# kam_rx.net
KiCad netlist of a schematic drawn in Altium Designer
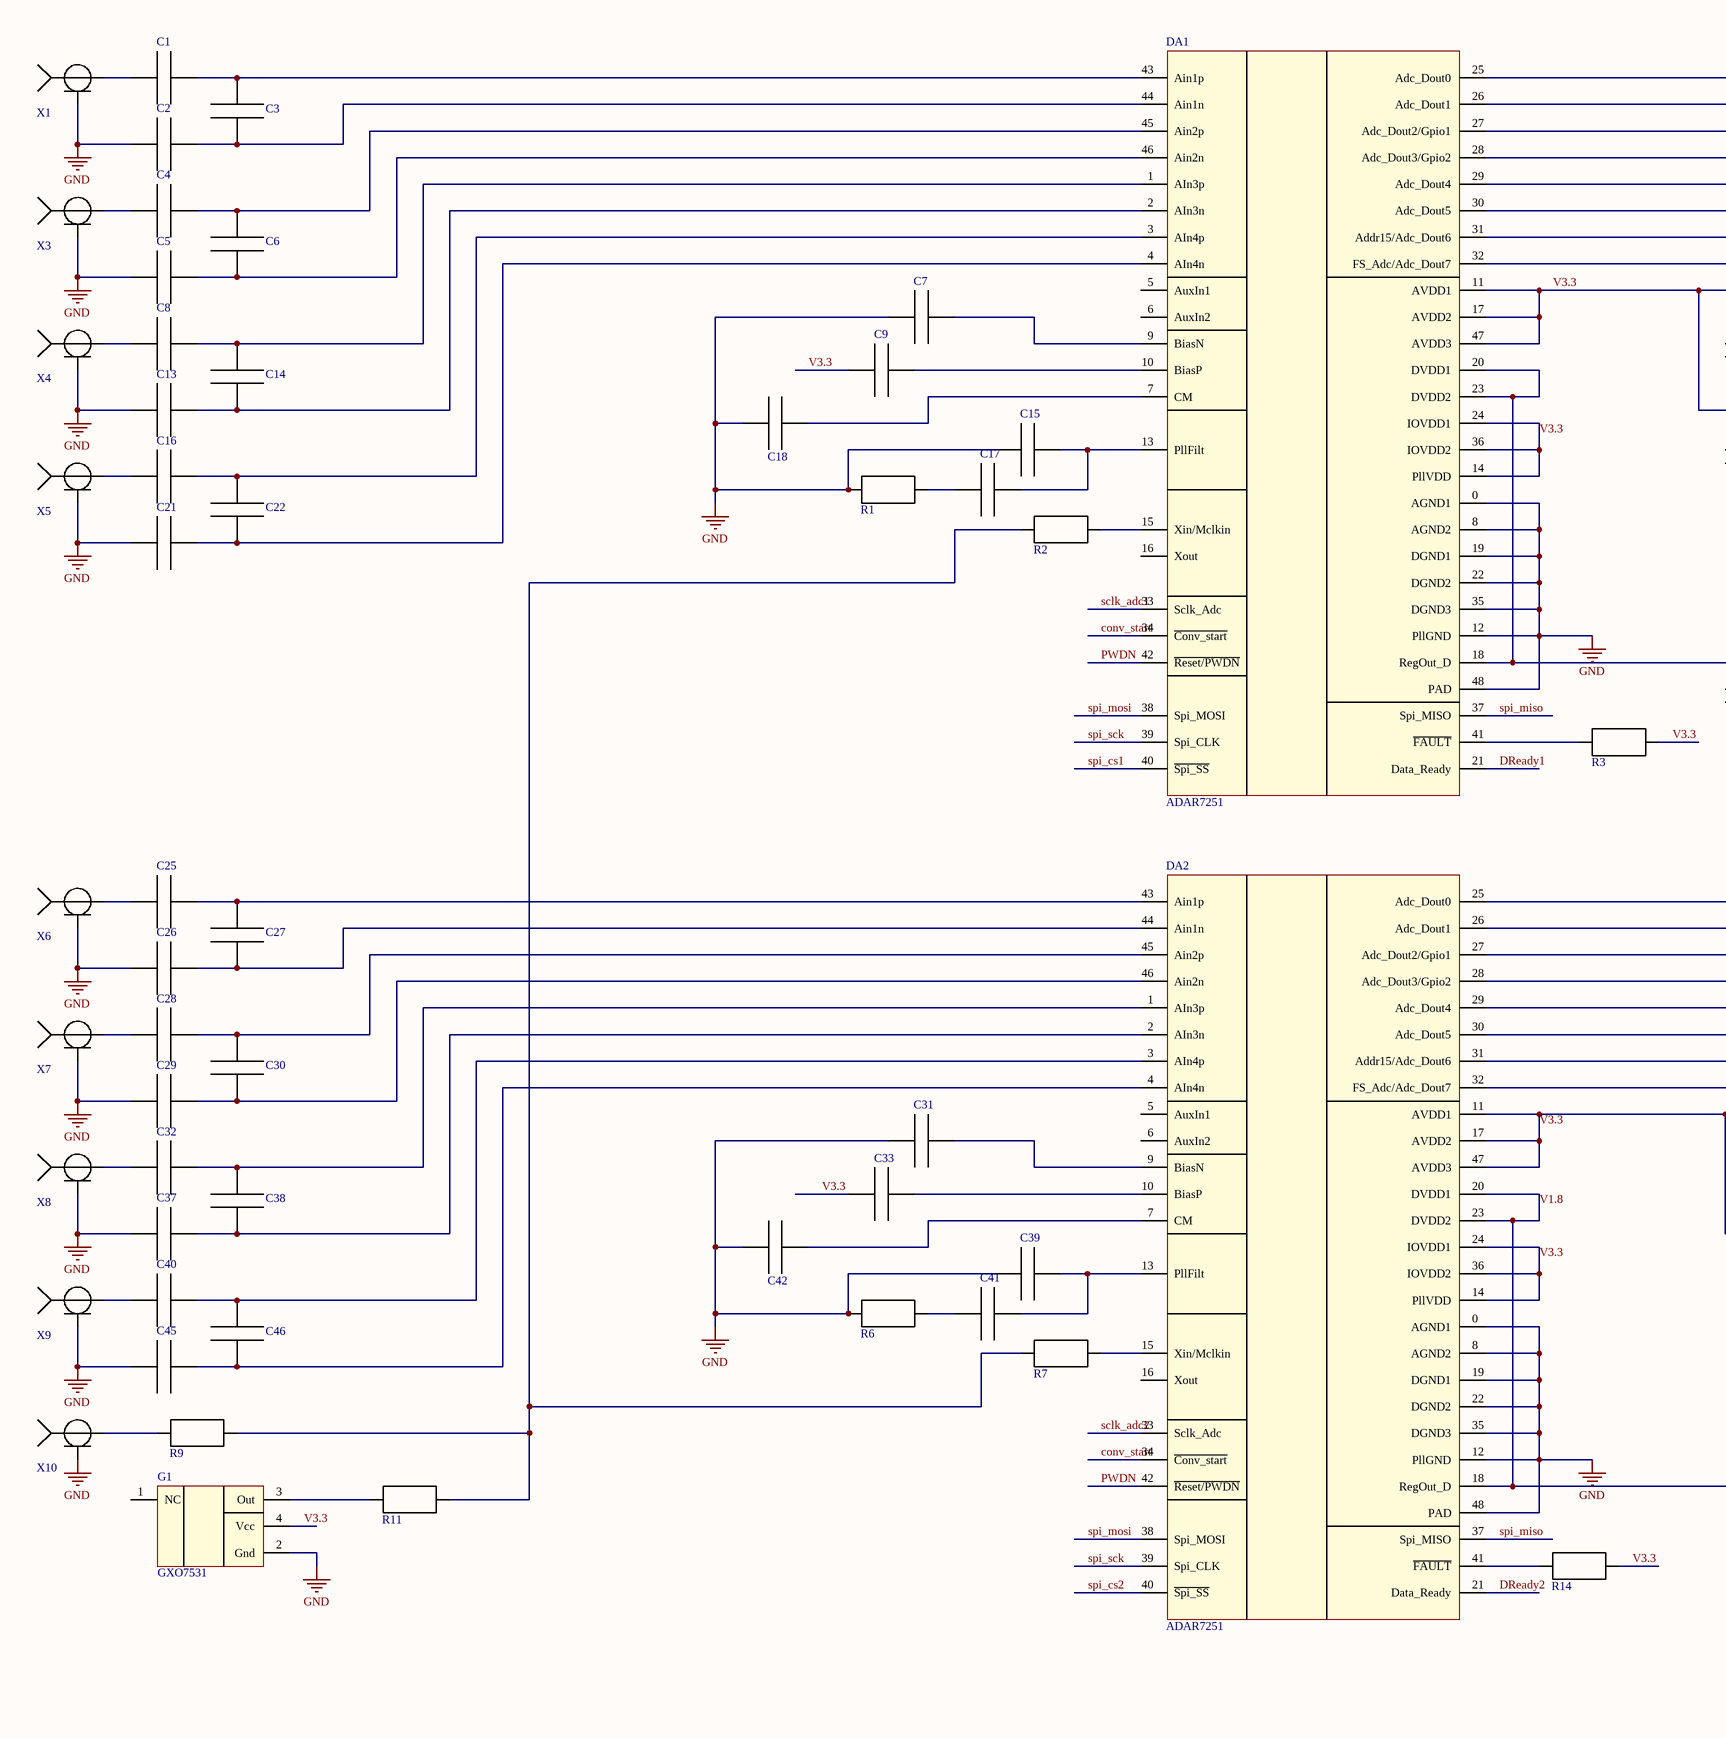
[diagram p0: kam_rx.SchDoc, left]
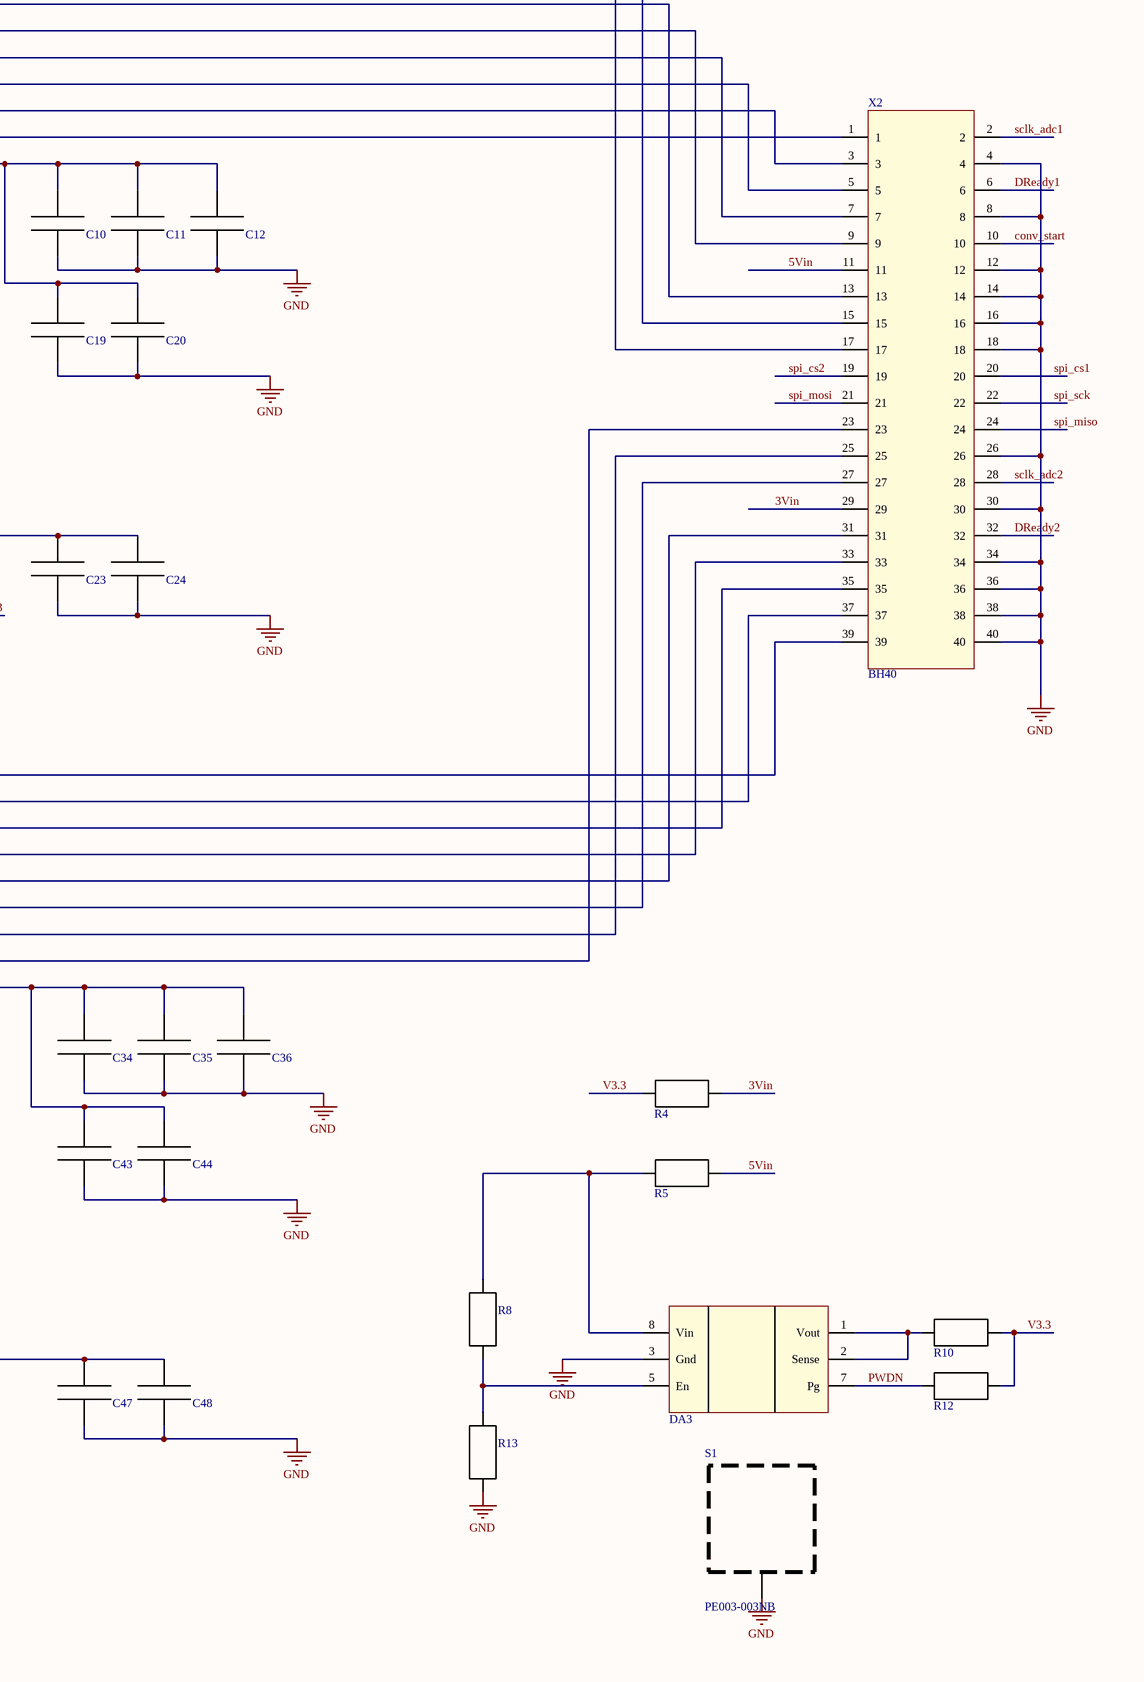
[diagram p1: kam_rx.SchDoc, right]

(export (version "E")
  (design (tool "Eeschema 10.0.6"))
  (components
    (comp (ref "C1")
      (value "C0603")
      (footprint "CAPC1608X06N")
      (libsource (lib "Integrated_Library") (part "C0603"))
    )
    (comp (ref "C2")
      (value "C0603")
      (footprint "CAPC1608X06N")
      (libsource (lib "Integrated_Library") (part "C0603"))
    )
    (comp (ref "C3")
      (value "C0603")
      (footprint "CAPC1608X06N")
      (libsource (lib "Integrated_Library") (part "C0603"))
    )
    (comp (ref "C4")
      (value "C0603")
      (footprint "CAPC1608X06N")
      (libsource (lib "Integrated_Library") (part "C0603"))
    )
    (comp (ref "C5")
      (value "C0603")
      (footprint "CAPC1608X06N")
      (libsource (lib "Integrated_Library") (part "C0603"))
    )
    (comp (ref "C6")
      (value "C0603")
      (footprint "CAPC1608X06N")
      (libsource (lib "Integrated_Library") (part "C0603"))
    )
    (comp (ref "C7")
      (value "C0603")
      (footprint "CAPC1608X06N")
      (libsource (lib "Integrated_Library") (part "C0603"))
    )
    (comp (ref "C8")
      (value "C0603")
      (footprint "CAPC1608X06N")
      (libsource (lib "Integrated_Library") (part "C0603"))
    )
    (comp (ref "C9")
      (value "C0603")
      (footprint "CAPC1608X06N")
      (libsource (lib "Integrated_Library") (part "C0603"))
    )
    (comp (ref "C10")
      (value "C0603")
      (footprint "CAPC1608X06N")
      (libsource (lib "Integrated_Library") (part "C0603"))
    )
    (comp (ref "C11")
      (value "C0603")
      (footprint "CAPC1608X06N")
      (libsource (lib "Integrated_Library") (part "C0603"))
    )
    (comp (ref "C12")
      (value "C0603")
      (footprint "CAPC1608X06N")
      (libsource (lib "Integrated_Library") (part "C0603"))
    )
    (comp (ref "C13")
      (value "C0603")
      (footprint "CAPC1608X06N")
      (libsource (lib "Integrated_Library") (part "C0603"))
    )
    (comp (ref "C14")
      (value "C0603")
      (footprint "CAPC1608X06N")
      (libsource (lib "Integrated_Library") (part "C0603"))
    )
    (comp (ref "C15")
      (value "C0603")
      (footprint "CAPC1608X06N")
      (libsource (lib "Integrated_Library") (part "C0603"))
    )
    (comp (ref "C16")
      (value "C0603")
      (footprint "CAPC1608X06N")
      (libsource (lib "Integrated_Library") (part "C0603"))
    )
    (comp (ref "C17")
      (value "C0603")
      (footprint "CAPC1608X06N")
      (libsource (lib "Integrated_Library") (part "C0603"))
    )
    (comp (ref "C18")
      (value "C0603")
      (footprint "CAPC1608X06N")
      (libsource (lib "Integrated_Library") (part "C0603"))
    )
    (comp (ref "C19")
      (value "C0603")
      (footprint "CAPC1608X06N")
      (libsource (lib "Integrated_Library") (part "C0603"))
    )
    (comp (ref "C20")
      (value "C0603")
      (footprint "CAPC1608X06N")
      (libsource (lib "Integrated_Library") (part "C0603"))
    )
    (comp (ref "C21")
      (value "C0603")
      (footprint "CAPC1608X06N")
      (libsource (lib "Integrated_Library") (part "C0603"))
    )
    (comp (ref "C22")
      (value "C0603")
      (footprint "CAPC1608X06N")
      (libsource (lib "Integrated_Library") (part "C0603"))
    )
    (comp (ref "C23")
      (value "C0603")
      (footprint "CAPC1608X06N")
      (libsource (lib "Integrated_Library") (part "C0603"))
    )
    (comp (ref "C24")
      (value "C0603")
      (footprint "CAPC1608X06N")
      (libsource (lib "Integrated_Library") (part "C0603"))
    )
    (comp (ref "C25")
      (value "C0603")
      (footprint "CAPC1608X06N")
      (libsource (lib "Integrated_Library") (part "C0603"))
    )
    (comp (ref "C26")
      (value "C0603")
      (footprint "CAPC1608X06N")
      (libsource (lib "Integrated_Library") (part "C0603"))
    )
    (comp (ref "C27")
      (value "C0603")
      (footprint "CAPC1608X06N")
      (libsource (lib "Integrated_Library") (part "C0603"))
    )
    (comp (ref "C28")
      (value "C0603")
      (footprint "CAPC1608X06N")
      (libsource (lib "Integrated_Library") (part "C0603"))
    )
    (comp (ref "C29")
      (value "C0603")
      (footprint "CAPC1608X06N")
      (libsource (lib "Integrated_Library") (part "C0603"))
    )
    (comp (ref "C30")
      (value "C0603")
      (footprint "CAPC1608X06N")
      (libsource (lib "Integrated_Library") (part "C0603"))
    )
    (comp (ref "C31")
      (value "C0603")
      (footprint "CAPC1608X06N")
      (libsource (lib "Integrated_Library") (part "C0603"))
    )
    (comp (ref "C32")
      (value "C0603")
      (footprint "CAPC1608X06N")
      (libsource (lib "Integrated_Library") (part "C0603"))
    )
    (comp (ref "C33")
      (value "C0603")
      (footprint "CAPC1608X06N")
      (libsource (lib "Integrated_Library") (part "C0603"))
    )
    (comp (ref "C34")
      (value "C0603")
      (footprint "CAPC1608X06N")
      (libsource (lib "Integrated_Library") (part "C0603"))
    )
    (comp (ref "C35")
      (value "C0603")
      (footprint "CAPC1608X06N")
      (libsource (lib "Integrated_Library") (part "C0603"))
    )
    (comp (ref "C36")
      (value "C0603")
      (footprint "CAPC1608X06N")
      (libsource (lib "Integrated_Library") (part "C0603"))
    )
    (comp (ref "C37")
      (value "C0603")
      (footprint "CAPC1608X06N")
      (libsource (lib "Integrated_Library") (part "C0603"))
    )
    (comp (ref "C38")
      (value "C0603")
      (footprint "CAPC1608X06N")
      (libsource (lib "Integrated_Library") (part "C0603"))
    )
    (comp (ref "C39")
      (value "C0603")
      (footprint "CAPC1608X06N")
      (libsource (lib "Integrated_Library") (part "C0603"))
    )
    (comp (ref "C40")
      (value "C0603")
      (footprint "CAPC1608X06N")
      (libsource (lib "Integrated_Library") (part "C0603"))
    )
    (comp (ref "C41")
      (value "C0603")
      (footprint "CAPC1608X06N")
      (libsource (lib "Integrated_Library") (part "C0603"))
    )
    (comp (ref "C42")
      (value "C0603")
      (footprint "CAPC1608X06N")
      (libsource (lib "Integrated_Library") (part "C0603"))
    )
    (comp (ref "C43")
      (value "C0603")
      (footprint "CAPC1608X06N")
      (libsource (lib "Integrated_Library") (part "C0603"))
    )
    (comp (ref "C44")
      (value "C0603")
      (footprint "CAPC1608X06N")
      (libsource (lib "Integrated_Library") (part "C0603"))
    )
    (comp (ref "C45")
      (value "C0603")
      (footprint "CAPC1608X06N")
      (libsource (lib "Integrated_Library") (part "C0603"))
    )
    (comp (ref "C46")
      (value "C0603")
      (footprint "CAPC1608X06N")
      (libsource (lib "Integrated_Library") (part "C0603"))
    )
    (comp (ref "C47")
      (value "C0603")
      (footprint "CAPC1608X06N")
      (libsource (lib "Integrated_Library") (part "C0603"))
    )
    (comp (ref "C48")
      (value "C0603")
      (footprint "CAPC1608X06N")
      (libsource (lib "Integrated_Library") (part "C0603"))
    )
    (comp (ref "DA1")
      (value "ADAR7251")
      (footprint "PQFN50P700X700X100_HS-49N")
      (libsource (lib "Integrated_Library") (part "ADAR7251"))
    )
    (comp (ref "DA2")
      (value "ADAR7251")
      (footprint "PQFN50P700X700X100_HS-49N")
      (libsource (lib "Integrated_Library") (part "ADAR7251"))
    )
    (comp (ref "DA3")
      (value "ADP7104")
      (footprint "SOIC127P600X165_HS-9N")
      (libsource (lib "Integrated_Library") (part "ADP7104"))
    )
    (comp (ref "G1")
      (value "GXO7531")
      (footprint "DFN400P700X145-4N")
      (libsource (lib "Integrated_Library") (part "GXO7531"))
    )
    (comp (ref "R1")
      (value "R0603")
      (footprint "RESC1608X06N")
      (libsource (lib "Integrated_Library") (part "R0603"))
    )
    (comp (ref "R2")
      (value "R0603")
      (footprint "RESC1608X06N")
      (libsource (lib "Integrated_Library") (part "R0603"))
    )
    (comp (ref "R3")
      (value "R0603")
      (footprint "RESC1608X06N")
      (libsource (lib "Integrated_Library") (part "R0603"))
    )
    (comp (ref "R4")
      (value "R0603")
      (footprint "RESC1608X06N")
      (libsource (lib "Integrated_Library") (part "R0603"))
    )
    (comp (ref "R5")
      (value "R0603")
      (footprint "RESC1608X06N")
      (libsource (lib "Integrated_Library") (part "R0603"))
    )
    (comp (ref "R6")
      (value "R0603")
      (footprint "RESC1608X06N")
      (libsource (lib "Integrated_Library") (part "R0603"))
    )
    (comp (ref "R7")
      (value "R0603")
      (footprint "RESC1608X06N")
      (libsource (lib "Integrated_Library") (part "R0603"))
    )
    (comp (ref "R8")
      (value "R0603")
      (footprint "RESC1608X06N")
      (libsource (lib "Integrated_Library") (part "R0603"))
    )
    (comp (ref "R9")
      (value "R0603")
      (footprint "RESC1608X06N")
      (libsource (lib "Integrated_Library") (part "R0603"))
    )
    (comp (ref "R10")
      (value "R0603")
      (footprint "RESC1608X06N")
      (libsource (lib "Integrated_Library") (part "R0603"))
    )
    (comp (ref "R11")
      (value "R0603")
      (footprint "RESC1608X06N")
      (libsource (lib "Integrated_Library") (part "R0603"))
    )
    (comp (ref "R12")
      (value "R0603")
      (footprint "RESC1608X06N")
      (libsource (lib "Integrated_Library") (part "R0603"))
    )
    (comp (ref "R13")
      (value "R0603")
      (footprint "RESC1608X06N")
      (libsource (lib "Integrated_Library") (part "R0603"))
    )
    (comp (ref "R14")
      (value "R0603")
      (footprint "RESC1608X06N")
      (libsource (lib "Integrated_Library") (part "R0603"))
    )
    (comp (ref "S1")
      (value "PE003-003NB")
      (footprint "PE003-003NB")
      (libsource (lib "Integrated_Library") (part "PE003-003NB"))
    )
    (comp (ref "X1")
      (value "MCX 1085221-1")
      (footprint "MCX")
      (libsource (lib "Integrated_Library") (part "MCX 1085221-1"))
    )
    (comp (ref "X2") (value "BH40") (footprint "BH40") (libsource (lib "Integrated_Library") (part "BH40")))
    (comp (ref "X3")
      (value "MCX 1085221-1")
      (footprint "MCX")
      (libsource (lib "Integrated_Library") (part "MCX 1085221-1"))
    )
    (comp (ref "X4")
      (value "MCX 1085221-1")
      (footprint "MCX")
      (libsource (lib "Integrated_Library") (part "MCX 1085221-1"))
    )
    (comp (ref "X5")
      (value "MCX 1085221-1")
      (footprint "MCX")
      (libsource (lib "Integrated_Library") (part "MCX 1085221-1"))
    )
    (comp (ref "X6")
      (value "MCX 1085221-1")
      (footprint "MCX")
      (libsource (lib "Integrated_Library") (part "MCX 1085221-1"))
    )
    (comp (ref "X7")
      (value "MCX 1085221-1")
      (footprint "MCX")
      (libsource (lib "Integrated_Library") (part "MCX 1085221-1"))
    )
    (comp (ref "X8")
      (value "MCX 1085221-1")
      (footprint "MCX")
      (libsource (lib "Integrated_Library") (part "MCX 1085221-1"))
    )
    (comp (ref "X9")
      (value "MCX 1085221-1")
      (footprint "MCX")
      (libsource (lib "Integrated_Library") (part "MCX 1085221-1"))
    )
    (comp (ref "X10")
      (value "MCX 1085221-1")
      (footprint "MCX")
      (libsource (lib "Integrated_Library") (part "MCX 1085221-1"))
    )
  )
  (nets
    (net (code "1") (name "/3Vin") (class "Default")
      (node (ref "R4") (pin "1") (pinfunction "1_1") (pintype "passive"))
      (node (ref "X2") (pin "29") (pinfunction "29_29") (pintype "passive"))
    )
    (net (code "2") (name "/5Vin") (class "Default")
      (node (ref "R5") (pin "1") (pinfunction "1_1") (pintype "passive"))
      (node (ref "X2") (pin "11") (pinfunction "11_11") (pintype "passive"))
    )
    (net (code "3") (name "/DReady1") (class "Default")
      (node (ref "DA1") (pin "21") (pinfunction "Data_Ready_21") (pintype "passive"))
      (node (ref "X2") (pin "6") (pinfunction "6_6") (pintype "passive"))
    )
    (net (code "4") (name "/DReady2") (class "Default")
      (node (ref "DA2") (pin "21") (pinfunction "Data_Ready_21") (pintype "passive"))
      (node (ref "X2") (pin "32") (pinfunction "32_32") (pintype "passive"))
    )
    (net (code "5") (name "/PWDN") (class "Default")
      (node (ref "DA1") (pin "42") (pinfunction "~{Reset/PWDN}_42") (pintype "passive"))
      (node (ref "DA2") (pin "42") (pinfunction "~{Reset/PWDN}_42") (pintype "passive"))
      (node (ref "DA3") (pin "7") (pinfunction "Pg_7") (pintype "passive"))
      (node (ref "R12") (pin "2") (pinfunction "2_2") (pintype "passive"))
    )
    (net (code "6") (name "/V1.8") (class "Default")
      (node (ref "C47") (pin "1") (pinfunction "1_1") (pintype "passive"))
      (node (ref "C48") (pin "1") (pinfunction "1_1") (pintype "passive"))
      (node (ref "DA2") (pin "18") (pinfunction "RegOut_D_18") (pintype "passive"))
      (node (ref "DA2") (pin "20") (pinfunction "DVDD1_20") (pintype "passive"))
      (node (ref "DA2") (pin "23") (pinfunction "DVDD2_23") (pintype "passive"))
    )
    (net (code "7") (name "/V3.3") (class "Default")
      (node (ref "C10") (pin "1") (pinfunction "1_1") (pintype "passive"))
      (node (ref "C11") (pin "1") (pinfunction "1_1") (pintype "passive"))
      (node (ref "C12") (pin "1") (pinfunction "1_1") (pintype "passive"))
      (node (ref "C19") (pin "1") (pinfunction "1_1") (pintype "passive"))
      (node (ref "C20") (pin "1") (pinfunction "1_1") (pintype "passive"))
      (node (ref "C33") (pin "1") (pinfunction "1_1") (pintype "passive"))
      (node (ref "C34") (pin "1") (pinfunction "1_1") (pintype "passive"))
      (node (ref "C35") (pin "1") (pinfunction "1_1") (pintype "passive"))
      (node (ref "C36") (pin "1") (pinfunction "1_1") (pintype "passive"))
      (node (ref "C43") (pin "1") (pinfunction "1_1") (pintype "passive"))
      (node (ref "C44") (pin "1") (pinfunction "1_1") (pintype "passive"))
      (node (ref "C9") (pin "1") (pinfunction "1_1") (pintype "passive"))
      (node (ref "DA1") (pin "11") (pinfunction "AVDD1_11") (pintype "passive"))
      (node (ref "DA1") (pin "14") (pinfunction "PllVDD_14") (pintype "passive"))
      (node (ref "DA1") (pin "17") (pinfunction "AVDD2_17") (pintype "passive"))
      (node (ref "DA1") (pin "24") (pinfunction "IOVDD1_24") (pintype "passive"))
      (node (ref "DA1") (pin "36") (pinfunction "IOVDD2_36") (pintype "passive"))
      (node (ref "DA1") (pin "47") (pinfunction "AVDD3_47") (pintype "passive"))
      (node (ref "DA2") (pin "11") (pinfunction "AVDD1_11") (pintype "passive"))
      (node (ref "DA2") (pin "14") (pinfunction "PllVDD_14") (pintype "passive"))
      (node (ref "DA2") (pin "17") (pinfunction "AVDD2_17") (pintype "passive"))
      (node (ref "DA2") (pin "24") (pinfunction "IOVDD1_24") (pintype "passive"))
      (node (ref "DA2") (pin "36") (pinfunction "IOVDD2_36") (pintype "passive"))
      (node (ref "DA2") (pin "47") (pinfunction "AVDD3_47") (pintype "passive"))
      (node (ref "G1") (pin "4") (pinfunction "Vcc_4") (pintype "passive"))
      (node (ref "R10") (pin "1") (pinfunction "1_1") (pintype "passive"))
      (node (ref "R12") (pin "1") (pinfunction "1_1") (pintype "passive"))
      (node (ref "R14") (pin "1") (pinfunction "1_1") (pintype "passive"))
      (node (ref "R3") (pin "1") (pinfunction "1_1") (pintype "passive"))
      (node (ref "R4") (pin "2") (pinfunction "2_2") (pintype "passive"))
    )
    (net (code "8") (name "/conv_start") (class "Default")
      (node (ref "DA1") (pin "34") (pinfunction "~{Conv_start}_34") (pintype "passive"))
      (node (ref "DA2") (pin "34") (pinfunction "~{Conv_start}_34") (pintype "passive"))
      (node (ref "X2") (pin "10") (pinfunction "10_10") (pintype "passive"))
    )
    (net (code "9") (name "/sclk_adc1") (class "Default")
      (node (ref "DA1") (pin "33") (pinfunction "Sclk_Adc_33") (pintype "passive"))
      (node (ref "X2") (pin "2") (pinfunction "2_2") (pintype "passive"))
    )
    (net (code "10") (name "/sclk_adc2") (class "Default")
      (node (ref "DA2") (pin "33") (pinfunction "Sclk_Adc_33") (pintype "passive"))
      (node (ref "X2") (pin "28") (pinfunction "28_28") (pintype "passive"))
    )
    (net (code "11") (name "/spi_cs1") (class "Default")
      (node (ref "DA1") (pin "40") (pinfunction "~{Spi_SS}_40") (pintype "passive"))
      (node (ref "X2") (pin "20") (pinfunction "20_20") (pintype "passive"))
    )
    (net (code "12") (name "/spi_cs2") (class "Default")
      (node (ref "DA2") (pin "40") (pinfunction "~{Spi_SS}_40") (pintype "passive"))
      (node (ref "X2") (pin "19") (pinfunction "19_19") (pintype "passive"))
    )
    (net (code "13") (name "/spi_miso") (class "Default")
      (node (ref "DA1") (pin "37") (pinfunction "Spi_MISO_37") (pintype "passive"))
      (node (ref "DA2") (pin "37") (pinfunction "Spi_MISO_37") (pintype "passive"))
      (node (ref "X2") (pin "24") (pinfunction "24_24") (pintype "passive"))
    )
    (net (code "14") (name "/spi_mosi") (class "Default")
      (node (ref "DA1") (pin "38") (pinfunction "Spi_MOSI_38") (pintype "passive"))
      (node (ref "DA2") (pin "38") (pinfunction "Spi_MOSI_38") (pintype "passive"))
      (node (ref "X2") (pin "21") (pinfunction "21_21") (pintype "passive"))
    )
    (net (code "15") (name "/spi_sck") (class "Default")
      (node (ref "DA1") (pin "39") (pinfunction "Spi_CLK_39") (pintype "passive"))
      (node (ref "DA2") (pin "39") (pinfunction "Spi_CLK_39") (pintype "passive"))
      (node (ref "X2") (pin "22") (pinfunction "22_22") (pintype "passive"))
    )
    (net (code "16") (name "GND") (class "Default")
      (node (ref "C10") (pin "2") (pinfunction "2_2") (pintype "passive"))
      (node (ref "C11") (pin "2") (pinfunction "2_2") (pintype "passive"))
      (node (ref "C12") (pin "2") (pinfunction "2_2") (pintype "passive"))
      (node (ref "C13") (pin "1") (pinfunction "1_1") (pintype "passive"))
      (node (ref "C15") (pin "1") (pinfunction "1_1") (pintype "passive"))
      (node (ref "C18") (pin "2") (pinfunction "2_2") (pintype "passive"))
      (node (ref "C19") (pin "2") (pinfunction "2_2") (pintype "passive"))
      (node (ref "C2") (pin "1") (pinfunction "1_1") (pintype "passive"))
      (node (ref "C20") (pin "2") (pinfunction "2_2") (pintype "passive"))
      (node (ref "C21") (pin "1") (pinfunction "1_1") (pintype "passive"))
      (node (ref "C23") (pin "2") (pinfunction "2_2") (pintype "passive"))
      (node (ref "C24") (pin "2") (pinfunction "2_2") (pintype "passive"))
      (node (ref "C26") (pin "1") (pinfunction "1_1") (pintype "passive"))
      (node (ref "C29") (pin "1") (pinfunction "1_1") (pintype "passive"))
      (node (ref "C31") (pin "1") (pinfunction "1_1") (pintype "passive"))
      (node (ref "C34") (pin "2") (pinfunction "2_2") (pintype "passive"))
      (node (ref "C35") (pin "2") (pinfunction "2_2") (pintype "passive"))
      (node (ref "C36") (pin "2") (pinfunction "2_2") (pintype "passive"))
      (node (ref "C37") (pin "1") (pinfunction "1_1") (pintype "passive"))
      (node (ref "C39") (pin "1") (pinfunction "1_1") (pintype "passive"))
      (node (ref "C42") (pin "2") (pinfunction "2_2") (pintype "passive"))
      (node (ref "C43") (pin "2") (pinfunction "2_2") (pintype "passive"))
      (node (ref "C44") (pin "2") (pinfunction "2_2") (pintype "passive"))
      (node (ref "C45") (pin "1") (pinfunction "1_1") (pintype "passive"))
      (node (ref "C47") (pin "2") (pinfunction "2_2") (pintype "passive"))
      (node (ref "C48") (pin "2") (pinfunction "2_2") (pintype "passive"))
      (node (ref "C5") (pin "1") (pinfunction "1_1") (pintype "passive"))
      (node (ref "C7") (pin "1") (pinfunction "1_1") (pintype "passive"))
      (node (ref "DA1") (pin "0") (pinfunction "AGND1_0") (pintype "passive"))
      (node (ref "DA1") (pin "12") (pinfunction "PllGND_12") (pintype "passive"))
      (node (ref "DA1") (pin "19") (pinfunction "DGND1_19") (pintype "passive"))
      (node (ref "DA1") (pin "22") (pinfunction "DGND2_22") (pintype "passive"))
      (node (ref "DA1") (pin "35") (pinfunction "DGND3_35") (pintype "passive"))
      (node (ref "DA1") (pin "48") (pinfunction "PAD_48") (pintype "passive"))
      (node (ref "DA1") (pin "8") (pinfunction "AGND2_8") (pintype "passive"))
      (node (ref "DA2") (pin "0") (pinfunction "AGND1_0") (pintype "passive"))
      (node (ref "DA2") (pin "12") (pinfunction "PllGND_12") (pintype "passive"))
      (node (ref "DA2") (pin "19") (pinfunction "DGND1_19") (pintype "passive"))
      (node (ref "DA2") (pin "22") (pinfunction "DGND2_22") (pintype "passive"))
      (node (ref "DA2") (pin "35") (pinfunction "DGND3_35") (pintype "passive"))
      (node (ref "DA2") (pin "48") (pinfunction "PAD_48") (pintype "passive"))
      (node (ref "DA2") (pin "8") (pinfunction "AGND2_8") (pintype "passive"))
      (node (ref "DA3") (pin "3") (pinfunction "Gnd_3") (pintype "passive"))
      (node (ref "G1") (pin "2") (pinfunction "Gnd_2") (pintype "passive"))
      (node (ref "R1") (pin "2") (pinfunction "2_2") (pintype "passive"))
      (node (ref "R13") (pin "2") (pinfunction "2_2") (pintype "passive"))
      (node (ref "R6") (pin "2") (pinfunction "2_2") (pintype "passive"))
      (node (ref "S1") (pin "0") (pinfunction "0_0") (pintype "passive"))
      (node (ref "X1") (pin "2") (pinfunction "2_2") (pintype "passive"))
      (node (ref "X10") (pin "2") (pinfunction "2_2") (pintype "passive"))
      (node (ref "X2") (pin "12") (pinfunction "12_12") (pintype "passive"))
      (node (ref "X2") (pin "14") (pinfunction "14_14") (pintype "passive"))
      (node (ref "X2") (pin "16") (pinfunction "16_16") (pintype "passive"))
      (node (ref "X2") (pin "18") (pinfunction "18_18") (pintype "passive"))
      (node (ref "X2") (pin "26") (pinfunction "26_26") (pintype "passive"))
      (node (ref "X2") (pin "30") (pinfunction "30_30") (pintype "passive"))
      (node (ref "X2") (pin "34") (pinfunction "34_34") (pintype "passive"))
      (node (ref "X2") (pin "36") (pinfunction "36_36") (pintype "passive"))
      (node (ref "X2") (pin "38") (pinfunction "38_38") (pintype "passive"))
      (node (ref "X2") (pin "4") (pinfunction "4_4") (pintype "passive"))
      (node (ref "X2") (pin "40") (pinfunction "40_40") (pintype "passive"))
      (node (ref "X2") (pin "8") (pinfunction "8_8") (pintype "passive"))
      (node (ref "X3") (pin "2") (pinfunction "2_2") (pintype "passive"))
      (node (ref "X4") (pin "2") (pinfunction "2_2") (pintype "passive"))
      (node (ref "X5") (pin "2") (pinfunction "2_2") (pintype "passive"))
      (node (ref "X6") (pin "2") (pinfunction "2_2") (pintype "passive"))
      (node (ref "X7") (pin "2") (pinfunction "2_2") (pintype "passive"))
      (node (ref "X8") (pin "2") (pinfunction "2_2") (pintype "passive"))
      (node (ref "X9") (pin "2") (pinfunction "2_2") (pintype "passive"))
    )
    (net (code "17") (name "Net-(C1-Pad1)") (class "Default")
      (node (ref "C1") (pin "1") (pinfunction "1_1") (pintype "passive"))
      (node (ref "X1") (pin "1") (pinfunction "1_1") (pintype "passive"))
    )
    (net (code "18") (name "Net-(C4-Pad1)") (class "Default")
      (node (ref "C4") (pin "1") (pinfunction "1_1") (pintype "passive"))
      (node (ref "X3") (pin "1") (pinfunction "1_1") (pintype "passive"))
    )
    (net (code "19") (name "Net-(C8-Pad1)") (class "Default")
      (node (ref "C8") (pin "1") (pinfunction "1_1") (pintype "passive"))
      (node (ref "X4") (pin "1") (pinfunction "1_1") (pintype "passive"))
    )
    (net (code "20") (name "Net-(C16-Pad1)") (class "Default")
      (node (ref "C16") (pin "1") (pinfunction "1_1") (pintype "passive"))
      (node (ref "X5") (pin "1") (pinfunction "1_1") (pintype "passive"))
    )
    (net (code "21") (name "Net-(C17-Pad1)") (class "Default")
      (node (ref "C17") (pin "1") (pinfunction "1_1") (pintype "passive"))
      (node (ref "R1") (pin "1") (pinfunction "1_1") (pintype "passive"))
    )
    (net (code "22") (name "Net-(C25-Pad1)") (class "Default")
      (node (ref "C25") (pin "1") (pinfunction "1_1") (pintype "passive"))
      (node (ref "X6") (pin "1") (pinfunction "1_1") (pintype "passive"))
    )
    (net (code "23") (name "Net-(C28-Pad1)") (class "Default")
      (node (ref "C28") (pin "1") (pinfunction "1_1") (pintype "passive"))
      (node (ref "X7") (pin "1") (pinfunction "1_1") (pintype "passive"))
    )
    (net (code "24") (name "Net-(C32-Pad1)") (class "Default")
      (node (ref "C32") (pin "1") (pinfunction "1_1") (pintype "passive"))
      (node (ref "X8") (pin "1") (pinfunction "1_1") (pintype "passive"))
    )
    (net (code "25") (name "Net-(C40-Pad1)") (class "Default")
      (node (ref "C40") (pin "1") (pinfunction "1_1") (pintype "passive"))
      (node (ref "X9") (pin "1") (pinfunction "1_1") (pintype "passive"))
    )
    (net (code "26") (name "Net-(C41-Pad1)") (class "Default")
      (node (ref "C41") (pin "1") (pinfunction "1_1") (pintype "passive"))
      (node (ref "R6") (pin "1") (pinfunction "1_1") (pintype "passive"))
    )
    (net (code "27") (name "Net-(DA1-AIn3n)") (class "Default")
      (node (ref "C13") (pin "2") (pinfunction "2_2") (pintype "passive"))
      (node (ref "C14") (pin "1") (pinfunction "1_1") (pintype "passive"))
      (node (ref "DA1") (pin "2") (pinfunction "AIn3n_2") (pintype "passive"))
    )
    (net (code "28") (name "Net-(DA1-AIn3p)") (class "Default")
      (node (ref "C14") (pin "2") (pinfunction "2_2") (pintype "passive"))
      (node (ref "C8") (pin "2") (pinfunction "2_2") (pintype "passive"))
      (node (ref "DA1") (pin "1") (pinfunction "AIn3p_1") (pintype "passive"))
    )
    (net (code "29") (name "Net-(DA1-AIn4n)") (class "Default")
      (node (ref "C21") (pin "2") (pinfunction "2_2") (pintype "passive"))
      (node (ref "C22") (pin "1") (pinfunction "1_1") (pintype "passive"))
      (node (ref "DA1") (pin "4") (pinfunction "AIn4n_4") (pintype "passive"))
    )
    (net (code "30") (name "Net-(DA1-AIn4p)") (class "Default")
      (node (ref "C16") (pin "2") (pinfunction "2_2") (pintype "passive"))
      (node (ref "C22") (pin "2") (pinfunction "2_2") (pintype "passive"))
      (node (ref "DA1") (pin "3") (pinfunction "AIn4p_3") (pintype "passive"))
    )
    (net (code "31") (name "Net-(DA1-Adc_Dout0)") (class "Default")
      (node (ref "DA1") (pin "25") (pinfunction "Adc_Dout0_25") (pintype "passive"))
      (node (ref "X2") (pin "17") (pinfunction "17_17") (pintype "passive"))
    )
    (net (code "32") (name "Net-(DA1-Adc_Dout1)") (class "Default")
      (node (ref "DA1") (pin "26") (pinfunction "Adc_Dout1_26") (pintype "passive"))
      (node (ref "X2") (pin "15") (pinfunction "15_15") (pintype "passive"))
    )
    (net (code "33") (name "Net-(DA1-Adc_Dout2{slash}Gpio1)") (class "Default")
      (node (ref "DA1") (pin "27") (pinfunction "Adc_Dout2/Gpio1_27") (pintype "passive"))
      (node (ref "X2") (pin "13") (pinfunction "13_13") (pintype "passive"))
    )
    (net (code "34") (name "Net-(DA1-Adc_Dout3{slash}Gpio2)") (class "Default")
      (node (ref "DA1") (pin "28") (pinfunction "Adc_Dout3/Gpio2_28") (pintype "passive"))
      (node (ref "X2") (pin "9") (pinfunction "9_9") (pintype "passive"))
    )
    (net (code "35") (name "Net-(DA1-Adc_Dout4)") (class "Default")
      (node (ref "DA1") (pin "29") (pinfunction "Adc_Dout4_29") (pintype "passive"))
      (node (ref "X2") (pin "7") (pinfunction "7_7") (pintype "passive"))
    )
    (net (code "36") (name "Net-(DA1-Adc_Dout5)") (class "Default")
      (node (ref "DA1") (pin "30") (pinfunction "Adc_Dout5_30") (pintype "passive"))
      (node (ref "X2") (pin "5") (pinfunction "5_5") (pintype "passive"))
    )
    (net (code "37") (name "Net-(DA1-Addr15{slash}Adc_Dout6)") (class "Default")
      (node (ref "DA1") (pin "31") (pinfunction "Addr15/Adc_Dout6_31") (pintype "passive"))
      (node (ref "X2") (pin "3") (pinfunction "3_3") (pintype "passive"))
    )
    (net (code "38") (name "Net-(DA1-Ain1n)") (class "Default")
      (node (ref "C2") (pin "2") (pinfunction "2_2") (pintype "passive"))
      (node (ref "C3") (pin "1") (pinfunction "1_1") (pintype "passive"))
      (node (ref "DA1") (pin "44") (pinfunction "Ain1n_44") (pintype "passive"))
    )
    (net (code "39") (name "Net-(DA1-Ain1p)") (class "Default")
      (node (ref "C1") (pin "2") (pinfunction "2_2") (pintype "passive"))
      (node (ref "C3") (pin "2") (pinfunction "2_2") (pintype "passive"))
      (node (ref "DA1") (pin "43") (pinfunction "Ain1p_43") (pintype "passive"))
    )
    (net (code "40") (name "Net-(DA1-Ain2n)") (class "Default")
      (node (ref "C5") (pin "2") (pinfunction "2_2") (pintype "passive"))
      (node (ref "C6") (pin "1") (pinfunction "1_1") (pintype "passive"))
      (node (ref "DA1") (pin "46") (pinfunction "Ain2n_46") (pintype "passive"))
    )
    (net (code "41") (name "Net-(DA1-Ain2p)") (class "Default")
      (node (ref "C4") (pin "2") (pinfunction "2_2") (pintype "passive"))
      (node (ref "C6") (pin "2") (pinfunction "2_2") (pintype "passive"))
      (node (ref "DA1") (pin "45") (pinfunction "Ain2p_45") (pintype "passive"))
    )
    (net (code "42") (name "Net-(DA1-BiasN)") (class "Default")
      (node (ref "C7") (pin "2") (pinfunction "2_2") (pintype "passive"))
      (node (ref "DA1") (pin "9") (pinfunction "BiasN_9") (pintype "passive"))
    )
    (net (code "43") (name "Net-(DA1-BiasP)") (class "Default")
      (node (ref "C9") (pin "2") (pinfunction "2_2") (pintype "passive"))
      (node (ref "DA1") (pin "10") (pinfunction "BiasP_10") (pintype "passive"))
    )
    (net (code "44") (name "Net-(DA1-CM)") (class "Default")
      (node (ref "C18") (pin "1") (pinfunction "1_1") (pintype "passive"))
      (node (ref "DA1") (pin "7") (pinfunction "CM_7") (pintype "passive"))
    )
    (net (code "45") (name "Net-(DA1-DVDD1)") (class "Default")
      (node (ref "C23") (pin "1") (pinfunction "1_1") (pintype "passive"))
      (node (ref "C24") (pin "1") (pinfunction "1_1") (pintype "passive"))
      (node (ref "DA1") (pin "18") (pinfunction "RegOut_D_18") (pintype "passive"))
      (node (ref "DA1") (pin "20") (pinfunction "DVDD1_20") (pintype "passive"))
      (node (ref "DA1") (pin "23") (pinfunction "DVDD2_23") (pintype "passive"))
    )
    (net (code "46") (name "Net-(DA1-FS_Adc{slash}Adc_Dout7)") (class "Default")
      (node (ref "DA1") (pin "32") (pinfunction "FS_Adc/Adc_Dout7_32") (pintype "passive"))
      (node (ref "X2") (pin "1") (pinfunction "1_1") (pintype "passive"))
    )
    (net (code "47") (name "Net-(DA1-PllFilt)") (class "Default")
      (node (ref "C15") (pin "2") (pinfunction "2_2") (pintype "passive"))
      (node (ref "C17") (pin "2") (pinfunction "2_2") (pintype "passive"))
      (node (ref "DA1") (pin "13") (pinfunction "PllFilt_13") (pintype "passive"))
    )
    (net (code "48") (name "Net-(DA1-Xin{slash}Mclkin)") (class "Default")
      (node (ref "DA1") (pin "15") (pinfunction "Xin/Mclkin_15") (pintype "passive"))
      (node (ref "R2") (pin "1") (pinfunction "1_1") (pintype "passive"))
    )
    (net (code "49") (name "Net-(DA1-~{FAULT})") (class "Default")
      (node (ref "DA1") (pin "41") (pinfunction "~{FAULT}_41") (pintype "passive"))
      (node (ref "R3") (pin "2") (pinfunction "2_2") (pintype "passive"))
    )
    (net (code "50") (name "Net-(DA2-AIn3n)") (class "Default")
      (node (ref "C37") (pin "2") (pinfunction "2_2") (pintype "passive"))
      (node (ref "C38") (pin "1") (pinfunction "1_1") (pintype "passive"))
      (node (ref "DA2") (pin "2") (pinfunction "AIn3n_2") (pintype "passive"))
    )
    (net (code "51") (name "Net-(DA2-AIn3p)") (class "Default")
      (node (ref "C32") (pin "2") (pinfunction "2_2") (pintype "passive"))
      (node (ref "C38") (pin "2") (pinfunction "2_2") (pintype "passive"))
      (node (ref "DA2") (pin "1") (pinfunction "AIn3p_1") (pintype "passive"))
    )
    (net (code "52") (name "Net-(DA2-AIn4n)") (class "Default")
      (node (ref "C45") (pin "2") (pinfunction "2_2") (pintype "passive"))
      (node (ref "C46") (pin "1") (pinfunction "1_1") (pintype "passive"))
      (node (ref "DA2") (pin "4") (pinfunction "AIn4n_4") (pintype "passive"))
    )
    (net (code "53") (name "Net-(DA2-AIn4p)") (class "Default")
      (node (ref "C40") (pin "2") (pinfunction "2_2") (pintype "passive"))
      (node (ref "C46") (pin "2") (pinfunction "2_2") (pintype "passive"))
      (node (ref "DA2") (pin "3") (pinfunction "AIn4p_3") (pintype "passive"))
    )
    (net (code "54") (name "Net-(DA2-Adc_Dout0)") (class "Default")
      (node (ref "DA2") (pin "25") (pinfunction "Adc_Dout0_25") (pintype "passive"))
      (node (ref "X2") (pin "39") (pinfunction "39_39") (pintype "passive"))
    )
    (net (code "55") (name "Net-(DA2-Adc_Dout1)") (class "Default")
      (node (ref "DA2") (pin "26") (pinfunction "Adc_Dout1_26") (pintype "passive"))
      (node (ref "X2") (pin "37") (pinfunction "37_37") (pintype "passive"))
    )
    (net (code "56") (name "Net-(DA2-Adc_Dout2{slash}Gpio1)") (class "Default")
      (node (ref "DA2") (pin "27") (pinfunction "Adc_Dout2/Gpio1_27") (pintype "passive"))
      (node (ref "X2") (pin "35") (pinfunction "35_35") (pintype "passive"))
    )
    (net (code "57") (name "Net-(DA2-Adc_Dout3{slash}Gpio2)") (class "Default")
      (node (ref "DA2") (pin "28") (pinfunction "Adc_Dout3/Gpio2_28") (pintype "passive"))
      (node (ref "X2") (pin "33") (pinfunction "33_33") (pintype "passive"))
    )
    (net (code "58") (name "Net-(DA2-Adc_Dout4)") (class "Default")
      (node (ref "DA2") (pin "29") (pinfunction "Adc_Dout4_29") (pintype "passive"))
      (node (ref "X2") (pin "31") (pinfunction "31_31") (pintype "passive"))
    )
    (net (code "59") (name "Net-(DA2-Adc_Dout5)") (class "Default")
      (node (ref "DA2") (pin "30") (pinfunction "Adc_Dout5_30") (pintype "passive"))
      (node (ref "X2") (pin "27") (pinfunction "27_27") (pintype "passive"))
    )
    (net (code "60") (name "Net-(DA2-Addr15{slash}Adc_Dout6)") (class "Default")
      (node (ref "DA2") (pin "31") (pinfunction "Addr15/Adc_Dout6_31") (pintype "passive"))
      (node (ref "X2") (pin "25") (pinfunction "25_25") (pintype "passive"))
    )
    (net (code "61") (name "Net-(DA2-Ain1n)") (class "Default")
      (node (ref "C26") (pin "2") (pinfunction "2_2") (pintype "passive"))
      (node (ref "C27") (pin "1") (pinfunction "1_1") (pintype "passive"))
      (node (ref "DA2") (pin "44") (pinfunction "Ain1n_44") (pintype "passive"))
    )
    (net (code "62") (name "Net-(DA2-Ain1p)") (class "Default")
      (node (ref "C25") (pin "2") (pinfunction "2_2") (pintype "passive"))
      (node (ref "C27") (pin "2") (pinfunction "2_2") (pintype "passive"))
      (node (ref "DA2") (pin "43") (pinfunction "Ain1p_43") (pintype "passive"))
    )
    (net (code "63") (name "Net-(DA2-Ain2n)") (class "Default")
      (node (ref "C29") (pin "2") (pinfunction "2_2") (pintype "passive"))
      (node (ref "C30") (pin "1") (pinfunction "1_1") (pintype "passive"))
      (node (ref "DA2") (pin "46") (pinfunction "Ain2n_46") (pintype "passive"))
    )
    (net (code "64") (name "Net-(DA2-Ain2p)") (class "Default")
      (node (ref "C28") (pin "2") (pinfunction "2_2") (pintype "passive"))
      (node (ref "C30") (pin "2") (pinfunction "2_2") (pintype "passive"))
      (node (ref "DA2") (pin "45") (pinfunction "Ain2p_45") (pintype "passive"))
    )
    (net (code "65") (name "Net-(DA2-BiasN)") (class "Default")
      (node (ref "C31") (pin "2") (pinfunction "2_2") (pintype "passive"))
      (node (ref "DA2") (pin "9") (pinfunction "BiasN_9") (pintype "passive"))
    )
    (net (code "66") (name "Net-(DA2-BiasP)") (class "Default")
      (node (ref "C33") (pin "2") (pinfunction "2_2") (pintype "passive"))
      (node (ref "DA2") (pin "10") (pinfunction "BiasP_10") (pintype "passive"))
    )
    (net (code "67") (name "Net-(DA2-CM)") (class "Default")
      (node (ref "C42") (pin "1") (pinfunction "1_1") (pintype "passive"))
      (node (ref "DA2") (pin "7") (pinfunction "CM_7") (pintype "passive"))
    )
    (net (code "68") (name "Net-(DA2-FS_Adc{slash}Adc_Dout7)") (class "Default")
      (node (ref "DA2") (pin "32") (pinfunction "FS_Adc/Adc_Dout7_32") (pintype "passive"))
      (node (ref "X2") (pin "23") (pinfunction "23_23") (pintype "passive"))
    )
    (net (code "69") (name "Net-(DA2-PllFilt)") (class "Default")
      (node (ref "C39") (pin "2") (pinfunction "2_2") (pintype "passive"))
      (node (ref "C41") (pin "2") (pinfunction "2_2") (pintype "passive"))
      (node (ref "DA2") (pin "13") (pinfunction "PllFilt_13") (pintype "passive"))
    )
    (net (code "70") (name "Net-(DA2-Xin{slash}Mclkin)") (class "Default")
      (node (ref "DA2") (pin "15") (pinfunction "Xin/Mclkin_15") (pintype "passive"))
      (node (ref "R7") (pin "1") (pinfunction "1_1") (pintype "passive"))
    )
    (net (code "71") (name "Net-(DA2-~{FAULT})") (class "Default")
      (node (ref "DA2") (pin "41") (pinfunction "~{FAULT}_41") (pintype "passive"))
      (node (ref "R14") (pin "2") (pinfunction "2_2") (pintype "passive"))
    )
    (net (code "72") (name "Net-(DA3-En)") (class "Default")
      (node (ref "DA3") (pin "5") (pinfunction "En_5") (pintype "passive"))
      (node (ref "R13") (pin "1") (pinfunction "1_1") (pintype "passive"))
      (node (ref "R8") (pin "2") (pinfunction "2_2") (pintype "passive"))
    )
    (net (code "73") (name "Net-(DA3-Sense)") (class "Default")
      (node (ref "DA3") (pin "1") (pinfunction "Vout_1") (pintype "passive"))
      (node (ref "DA3") (pin "2") (pinfunction "Sense_2") (pintype "passive"))
      (node (ref "R10") (pin "2") (pinfunction "2_2") (pintype "passive"))
    )
    (net (code "74") (name "Net-(DA3-Vin)") (class "Default")
      (node (ref "DA3") (pin "8") (pinfunction "Vin_8") (pintype "passive"))
      (node (ref "R5") (pin "2") (pinfunction "2_2") (pintype "passive"))
      (node (ref "R8") (pin "1") (pinfunction "1_1") (pintype "passive"))
    )
    (net (code "75") (name "Net-(G1-Out)") (class "Default")
      (node (ref "G1") (pin "3") (pinfunction "Out_3") (pintype "passive"))
      (node (ref "R11") (pin "2") (pinfunction "2_2") (pintype "passive"))
    )
    (net (code "76") (name "Net-(R9-Pad2)") (class "Default")
      (node (ref "R9") (pin "2") (pinfunction "2_2") (pintype "passive"))
      (node (ref "X10") (pin "1") (pinfunction "1_1") (pintype "passive"))
    )
    (net (code "77") (name "Net-(R11-Pad1)") (class "Default")
      (node (ref "R11") (pin "1") (pinfunction "1_1") (pintype "passive"))
      (node (ref "R2") (pin "2") (pinfunction "2_2") (pintype "passive"))
      (node (ref "R7") (pin "2") (pinfunction "2_2") (pintype "passive"))
      (node (ref "R9") (pin "1") (pinfunction "1_1") (pintype "passive"))
    )
    (net (code "78") (name "unconnected-(DA1-AuxIn1-Pad5)") (class "Default")
      (node (ref "DA1") (pin "5") (pinfunction "AuxIn1_5") (pintype "passive"))
    )
    (net (code "79") (name "unconnected-(DA1-AuxIn2-Pad6)") (class "Default")
      (node (ref "DA1") (pin "6") (pinfunction "AuxIn2_6") (pintype "passive"))
    )
    (net (code "80") (name "unconnected-(DA1-Xout-Pad16)") (class "Default")
      (node (ref "DA1") (pin "16") (pinfunction "Xout_16") (pintype "passive"))
    )
    (net (code "81") (name "unconnected-(DA2-AuxIn1-Pad5)") (class "Default")
      (node (ref "DA2") (pin "5") (pinfunction "AuxIn1_5") (pintype "passive"))
    )
    (net (code "82") (name "unconnected-(DA2-AuxIn2-Pad6)") (class "Default")
      (node (ref "DA2") (pin "6") (pinfunction "AuxIn2_6") (pintype "passive"))
    )
    (net (code "83") (name "unconnected-(DA2-Xout-Pad16)") (class "Default")
      (node (ref "DA2") (pin "16") (pinfunction "Xout_16") (pintype "passive"))
    )
    (net (code "84") (name "unconnected-(G1-NC-Pad1)") (class "Default")
      (node (ref "G1") (pin "1") (pinfunction "NC_1") (pintype "passive"))
    )
  )
)
